# Voltage_Rails.net
KiCad netlist of a schematic drawn in Altium Designer
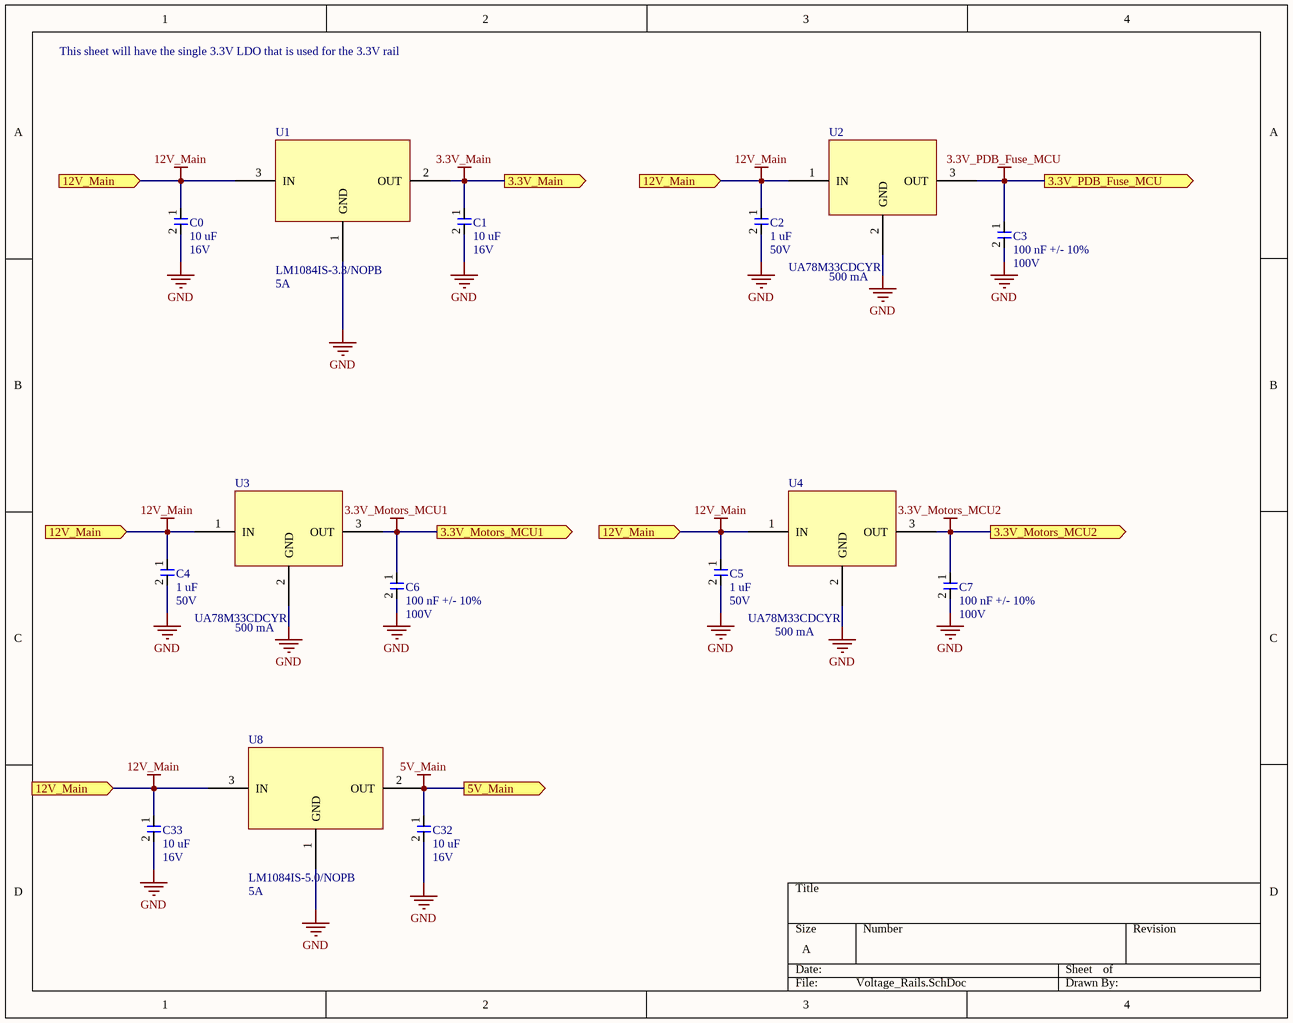
[diagram p0: Voltage_Rails.SchDoc]

(export (version "E")
  (design (tool "Eeschema 10.0.6"))
  (components
    (comp (ref "C0")
      (value "CL21A106KOQNNNE")
      (footprint "CAP-0805")
      (description "10 µF ±10% 16V Ceramic Capacitor X7R 0805 (2012 Metric)")
      (fields (field (name "CAPACITANCE") "10 uF") (field (name "VOLTAGE RATING") "16V"))
      (libsource (lib "MasterLib") (part "CAP-10U-0002"))
    )
    (comp (ref "C1")
      (value "CL21A106KOQNNNE")
      (footprint "CAP-0805")
      (description "10 µF ±10% 16V Ceramic Capacitor X7R 0805 (2012 Metric)")
      (fields (field (name "CAPACITANCE") "10 uF") (field (name "VOLTAGE RATING") "16V"))
      (libsource (lib "MasterLib") (part "CAP-10U-0002"))
    )
    (comp (ref "C2")
      (value "UMK107AB7105KA-T")
      (footprint "CAP-0603")
      (description "1 µF ±10% 50V Ceramic Capacitor X7R 0603 (1608 Metric)")
      (fields (field (name "CAPACITANCE") "1 uF") (field (name "VOLTAGE") "50V"))
      (libsource (lib "MasterLib") (part "CAP-1U-0002"))
    )
    (comp (ref "C3")
      (value "CC0603KRX7R0BB104")
      (footprint "CAP-0603")
      (description "100V 100nF X7R ±10% 0603 Multilayer Ceramic Capacitors MLCC - SMD/SMT ROHS")
      (fields
        (field (name "JLC PART NUMBER") "C113803")
        (field (name "CAPACITANCE") "100 nF +/- 10%")
        (field (name "VOLTAGE") "100V")
      )
      (libsource (lib "MasterLib") (part "CAP-100N-0002-JLC"))
    )
    (comp (ref "C4")
      (value "UMK107AB7105KA-T")
      (footprint "CAP-0603")
      (description "1 µF ±10% 50V Ceramic Capacitor X7R 0603 (1608 Metric)")
      (fields (field (name "CAPACITANCE") "1 uF") (field (name "VOLTAGE") "50V"))
      (libsource (lib "MasterLib") (part "CAP-1U-0002"))
    )
    (comp (ref "C5")
      (value "UMK107AB7105KA-T")
      (footprint "CAP-0603")
      (description "1 µF ±10% 50V Ceramic Capacitor X7R 0603 (1608 Metric)")
      (fields (field (name "CAPACITANCE") "1 uF") (field (name "VOLTAGE") "50V"))
      (libsource (lib "MasterLib") (part "CAP-1U-0002"))
    )
    (comp (ref "C6")
      (value "CC0603KRX7R0BB104")
      (footprint "CAP-0603")
      (description "100V 100nF X7R ±10% 0603 Multilayer Ceramic Capacitors MLCC - SMD/SMT ROHS")
      (fields
        (field (name "JLC PART NUMBER") "C113803")
        (field (name "CAPACITANCE") "100 nF +/- 10%")
        (field (name "VOLTAGE") "100V")
      )
      (libsource (lib "MasterLib") (part "CAP-100N-0002-JLC"))
    )
    (comp (ref "C7")
      (value "CC0603KRX7R0BB104")
      (footprint "CAP-0603")
      (description "100V 100nF X7R ±10% 0603 Multilayer Ceramic Capacitors MLCC - SMD/SMT ROHS")
      (fields
        (field (name "JLC PART NUMBER") "C113803")
        (field (name "CAPACITANCE") "100 nF +/- 10%")
        (field (name "VOLTAGE") "100V")
      )
      (libsource (lib "MasterLib") (part "CAP-100N-0002-JLC"))
    )
    (comp (ref "C32")
      (value "CL21A106KOQNNNE")
      (footprint "CAP-0805")
      (description "10 µF ±10% 16V Ceramic Capacitor X7R 0805 (2012 Metric)")
      (fields (field (name "CAPACITANCE") "10 uF") (field (name "VOLTAGE RATING") "16V"))
      (libsource (lib "MasterLib") (part "CAP-10U-0002"))
    )
    (comp (ref "C33")
      (value "CL21A106KOQNNNE")
      (footprint "CAP-0805")
      (description "10 µF ±10% 16V Ceramic Capacitor X7R 0805 (2012 Metric)")
      (fields (field (name "CAPACITANCE") "10 uF") (field (name "VOLTAGE RATING") "16V"))
      (libsource (lib "MasterLib") (part "CAP-10U-0002"))
    )
    (comp (ref "U1")
      (value "LM1084IS-3.3/NOPB")
      (footprint "DDPAK/TO-263-3")
      (description "Linear Voltage Regulator IC Positive Fixed 1 Output 5A DDPAK/TO-263-3")
      (fields (field (name "CURRENT") "5A"))
      (libsource (lib "MasterLib") (part "LDO-3.3V-0001"))
    )
    (comp (ref "U2")
      (value "UA78M33CDCYR")
      (footprint "SOT-223-4")
      (description "Linear Voltage Regulator IC Positive Fixed 1 Output 500mA SOT-223-4")
      (fields (field (name "CURRENT") "500 mA"))
      (libsource (lib "MasterLib") (part "LDO-3.3V-0002"))
    )
    (comp (ref "U3")
      (value "UA78M33CDCYR")
      (footprint "SOT-223-4")
      (description "Linear Voltage Regulator IC Positive Fixed 1 Output 500mA SOT-223-4")
      (fields (field (name "CURRENT") "500 mA"))
      (libsource (lib "MasterLib") (part "LDO-3.3V-0002"))
    )
    (comp (ref "U4")
      (value "UA78M33CDCYR")
      (footprint "SOT-223-4")
      (description "Linear Voltage Regulator IC Positive Fixed 1 Output 500mA SOT-223-4")
      (fields (field (name "CURRENT") "500 mA"))
      (libsource (lib "MasterLib") (part "LDO-3.3V-0002"))
    )
    (comp (ref "U8")
      (value "LM1084IS-5.0/NOPB")
      (footprint "DDPAK/TO-263-3")
      (description "Linear Voltage Regulator IC Positive Fixed 1 Output 5A DDPAK/TO-263-3")
      (fields (field (name "CURRENT") "5A"))
      (libsource (lib "MasterLib") (part "LDO-5V-0001"))
    )
  )
  (nets
    (net (code "1") (name "3.3V_Main") (class "Default")
      (node (ref "C1") (pin "1") (pinfunction "1_1") (pintype "passive"))
      (node (ref "U1") (pin "2") (pinfunction "OUT_2") (pintype "power_in"))
    )
    (net (code "2") (name "3.3V_Motors_MCU1") (class "Default")
      (node (ref "C6") (pin "1") (pinfunction "1_1") (pintype "passive"))
      (node (ref "U3") (pin "3") (pinfunction "OUT_3") (pintype "power_in"))
    )
    (net (code "3") (name "3.3V_Motors_MCU2") (class "Default")
      (node (ref "C7") (pin "1") (pinfunction "1_1") (pintype "passive"))
      (node (ref "U4") (pin "3") (pinfunction "OUT_3") (pintype "power_in"))
    )
    (net (code "4") (name "3.3V_PDB_Fuse_MCU") (class "Default")
      (node (ref "C3") (pin "1") (pinfunction "1_1") (pintype "passive"))
      (node (ref "U2") (pin "3") (pinfunction "OUT_3") (pintype "power_in"))
    )
    (net (code "5") (name "5V_Main") (class "Default")
      (node (ref "C32") (pin "1") (pinfunction "1_1") (pintype "passive"))
      (node (ref "U8") (pin "2") (pinfunction "OUT_2") (pintype "power_in"))
    )
    (net (code "6") (name "12V_Main") (class "Default")
      (node (ref "C0") (pin "1") (pinfunction "1_1") (pintype "passive"))
      (node (ref "C2") (pin "1") (pinfunction "1_1") (pintype "passive"))
      (node (ref "C33") (pin "1") (pinfunction "1_1") (pintype "passive"))
      (node (ref "C4") (pin "1") (pinfunction "1_1") (pintype "passive"))
      (node (ref "C5") (pin "1") (pinfunction "1_1") (pintype "passive"))
      (node (ref "U1") (pin "3") (pinfunction "IN_3") (pintype "power_in"))
      (node (ref "U2") (pin "1") (pinfunction "IN_1") (pintype "power_in"))
      (node (ref "U3") (pin "1") (pinfunction "IN_1") (pintype "power_in"))
      (node (ref "U4") (pin "1") (pinfunction "IN_1") (pintype "power_in"))
      (node (ref "U8") (pin "3") (pinfunction "IN_3") (pintype "power_in"))
    )
    (net (code "7") (name "GND") (class "Default")
      (node (ref "C0") (pin "2") (pinfunction "2_2") (pintype "passive"))
      (node (ref "C1") (pin "2") (pinfunction "2_2") (pintype "passive"))
      (node (ref "C2") (pin "2") (pinfunction "2_2") (pintype "passive"))
      (node (ref "C3") (pin "2") (pinfunction "2_2") (pintype "passive"))
      (node (ref "C32") (pin "2") (pinfunction "2_2") (pintype "passive"))
      (node (ref "C33") (pin "2") (pinfunction "2_2") (pintype "passive"))
      (node (ref "C4") (pin "2") (pinfunction "2_2") (pintype "passive"))
      (node (ref "C5") (pin "2") (pinfunction "2_2") (pintype "passive"))
      (node (ref "C6") (pin "2") (pinfunction "2_2") (pintype "passive"))
      (node (ref "C7") (pin "2") (pinfunction "2_2") (pintype "passive"))
      (node (ref "U1") (pin "1") (pinfunction "GND_1") (pintype "power_in"))
      (node (ref "U2") (pin "2") (pinfunction "GND_2") (pintype "power_in"))
      (node (ref "U3") (pin "2") (pinfunction "GND_2") (pintype "power_in"))
      (node (ref "U4") (pin "2") (pinfunction "GND_2") (pintype "power_in"))
      (node (ref "U8") (pin "1") (pinfunction "GND_1") (pintype "power_in"))
    )
  )
)
